# MB1297_MCU1.net
KiCad netlist of a schematic drawn in Altium Designer
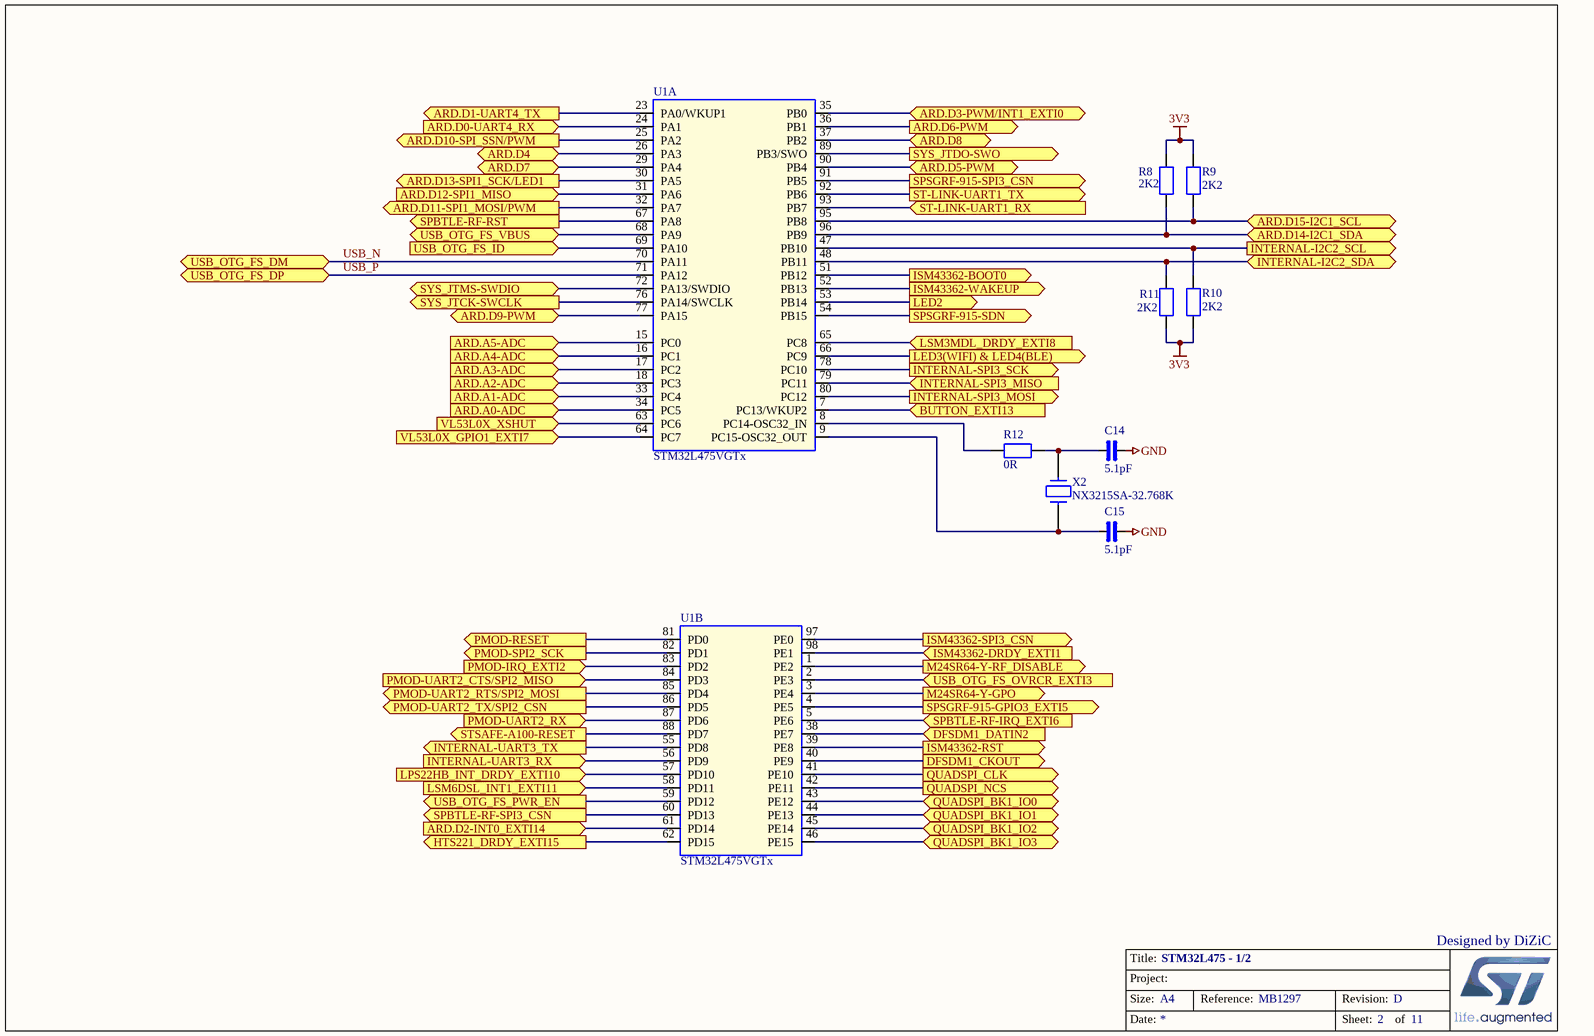
[diagram p0: MB1297_MCU1.SchDoc]

(export (version "E")
  (design (tool "Eeschema 10.0.6"))
  (components
    (comp (ref "C14")
      (value "5.1pF")
      (footprint "0402_CAP_NPOL")
      (description "Capacitor_not polarized")
      (libsource (lib "ST_Lib3D") (part "CAP_NPOL"))
    )
    (comp (ref "C15")
      (value "5.1pF")
      (footprint "0402_CAP_NPOL")
      (description "Capacitor_not polarized")
      (libsource (lib "ST_Lib3D") (part "CAP_NPOL"))
    )
    (comp (ref "R8")
      (value "2K2")
      (footprint "0402_RES")
      (description "Resistor")
      (libsource (lib "ST_Lib3D") (part "RES"))
    )
    (comp (ref "R9")
      (value "2K2")
      (footprint "0402_RES")
      (description "Resistor")
      (libsource (lib "ST_Lib3D") (part "RES"))
    )
    (comp (ref "R10")
      (value "2K2")
      (footprint "0402_RES")
      (description "Resistor")
      (libsource (lib "ST_Lib3D") (part "RES"))
    )
    (comp (ref "R11")
      (value "2K2")
      (footprint "0402_RES")
      (description "Resistor")
      (libsource (lib "ST_Lib3D") (part "RES"))
    )
    (comp (ref "R12")
      (value "0R")
      (footprint "0402_RES")
      (description "Resistor")
      (libsource (lib "ST_Lib3D") (part "RES"))
    )
    (comp (ref "U1")
      (value "STM32L475VGTx")
      (footprint "ST_Lib3D:LQFP100 14x14x1.6")
      (libsource (lib "ST_Lib3D") (part "STM32L475VGTx"))
    )
    (comp (ref "X2")
      (value "NX3215SA-32.768K")
      (footprint "CRY_NX3215SA_2P")
      (description "Crystal 32.768kHz, 6pF, -+20PPM, R=50K, SMD")
      (libsource (lib "MCD_TEMP_PCH") (part "XTAL_32K_NX3215SA"))
    )
  )
  (nets
    (net (code "1") (name "/ARD.A0-ADC") (class "Default")
      (node (ref "U1") (pin "34") (pinfunction "PC5_34") (pintype "passive"))
    )
    (net (code "2") (name "/ARD.A1-ADC") (class "Default")
      (node (ref "U1") (pin "33") (pinfunction "PC4_33") (pintype "passive"))
    )
    (net (code "3") (name "/ARD.A2-ADC") (class "Default")
      (node (ref "U1") (pin "18") (pinfunction "PC3_18") (pintype "passive"))
    )
    (net (code "4") (name "/ARD.A3-ADC") (class "Default")
      (node (ref "U1") (pin "17") (pinfunction "PC2_17") (pintype "passive"))
    )
    (net (code "5") (name "/ARD.A4-ADC") (class "Default")
      (node (ref "U1") (pin "16") (pinfunction "PC1_16") (pintype "passive"))
    )
    (net (code "6") (name "/ARD.A5-ADC") (class "Default")
      (node (ref "U1") (pin "15") (pinfunction "PC0_15") (pintype "passive"))
    )
    (net (code "7") (name "/ARD.D0-UART4_RX") (class "Default")
      (node (ref "U1") (pin "24") (pinfunction "PA1_24") (pintype "passive"))
    )
    (net (code "8") (name "/ARD.D1-UART4_TX") (class "Default")
      (node (ref "U1") (pin "23") (pinfunction "PA0/WKUP1_23") (pintype "passive"))
    )
    (net (code "9") (name "/ARD.D2-INT0_EXTI14") (class "Default")
      (node (ref "U1") (pin "61") (pinfunction "PD14_61") (pintype "passive"))
    )
    (net (code "10") (name "/ARD.D3-PWM{slash}INT1_EXTI0") (class "Default")
      (node (ref "U1") (pin "35") (pinfunction "PB0_35") (pintype "passive"))
    )
    (net (code "11") (name "/ARD.D4") (class "Default")
      (node (ref "U1") (pin "26") (pinfunction "PA3_26") (pintype "passive"))
    )
    (net (code "12") (name "/ARD.D5-PWM") (class "Default")
      (node (ref "U1") (pin "90") (pinfunction "PB4_90") (pintype "passive"))
    )
    (net (code "13") (name "/ARD.D6-PWM") (class "Default")
      (node (ref "U1") (pin "36") (pinfunction "PB1_36") (pintype "passive"))
    )
    (net (code "14") (name "/ARD.D7") (class "Default")
      (node (ref "U1") (pin "29") (pinfunction "PA4_29") (pintype "passive"))
    )
    (net (code "15") (name "/ARD.D8") (class "Default")
      (node (ref "U1") (pin "37") (pinfunction "PB2_37") (pintype "passive"))
    )
    (net (code "16") (name "/ARD.D9-PWM") (class "Default")
      (node (ref "U1") (pin "77") (pinfunction "PA15_77") (pintype "passive"))
    )
    (net (code "17") (name "/ARD.D10-SPI_SSN{slash}PWM") (class "Default")
      (node (ref "U1") (pin "25") (pinfunction "PA2_25") (pintype "passive"))
    )
    (net (code "18") (name "/ARD.D11-SPI1_MOSI{slash}PWM") (class "Default")
      (node (ref "U1") (pin "32") (pinfunction "PA7_32") (pintype "passive"))
    )
    (net (code "19") (name "/ARD.D12-SPI1_MISO") (class "Default")
      (node (ref "U1") (pin "31") (pinfunction "PA6_31") (pintype "passive"))
    )
    (net (code "20") (name "/ARD.D13-SPI1_SCK{slash}LED1") (class "Default")
      (node (ref "U1") (pin "30") (pinfunction "PA5_30") (pintype "passive"))
    )
    (net (code "21") (name "/ARD.D14-I2C1_SDA") (class "Default")
      (node (ref "R8") (pin "2") (pinfunction "2_2") (pintype "passive"))
      (node (ref "U1") (pin "96") (pinfunction "PB9_96") (pintype "passive"))
    )
    (net (code "22") (name "/ARD.D15-I2C1_SCL") (class "Default")
      (node (ref "R9") (pin "2") (pinfunction "2_2") (pintype "passive"))
      (node (ref "U1") (pin "95") (pinfunction "PB8_95") (pintype "passive"))
    )
    (net (code "23") (name "/BUTTON_EXTI13") (class "Default")
      (node (ref "U1") (pin "7") (pinfunction "PC13/WKUP2_7") (pintype "passive"))
    )
    (net (code "24") (name "/DFSDM1_CKOUT") (class "Default")
      (node (ref "U1") (pin "40") (pinfunction "PE9_40") (pintype "passive"))
    )
    (net (code "25") (name "/DFSDM1_DATIN2") (class "Default")
      (node (ref "U1") (pin "38") (pinfunction "PE7_38") (pintype "passive"))
    )
    (net (code "26") (name "/HTS221_DRDY_EXTI15") (class "Default")
      (node (ref "U1") (pin "62") (pinfunction "PD15_62") (pintype "passive"))
    )
    (net (code "27") (name "/INTERNAL-I2C2_SCL") (class "Default")
      (node (ref "R10") (pin "2") (pinfunction "2_2") (pintype "passive"))
      (node (ref "U1") (pin "47") (pinfunction "PB10_47") (pintype "passive"))
    )
    (net (code "28") (name "/INTERNAL-I2C2_SDA") (class "Default")
      (node (ref "R11") (pin "2") (pinfunction "2_2") (pintype "passive"))
      (node (ref "U1") (pin "48") (pinfunction "PB11_48") (pintype "passive"))
    )
    (net (code "29") (name "/INTERNAL-SPI3_MISO") (class "Default")
      (node (ref "U1") (pin "79") (pinfunction "PC11_79") (pintype "passive"))
    )
    (net (code "30") (name "/INTERNAL-SPI3_MOSI") (class "Default")
      (node (ref "U1") (pin "80") (pinfunction "PC12_80") (pintype "passive"))
    )
    (net (code "31") (name "/INTERNAL-SPI3_SCK") (class "Default")
      (node (ref "U1") (pin "78") (pinfunction "PC10_78") (pintype "passive"))
    )
    (net (code "32") (name "/INTERNAL-UART3_RX") (class "Default")
      (node (ref "U1") (pin "56") (pinfunction "PD9_56") (pintype "passive"))
    )
    (net (code "33") (name "/INTERNAL-UART3_TX") (class "Default")
      (node (ref "U1") (pin "55") (pinfunction "PD8_55") (pintype "passive"))
    )
    (net (code "34") (name "/ISM43362-BOOT0") (class "Default")
      (node (ref "U1") (pin "51") (pinfunction "PB12_51") (pintype "passive"))
    )
    (net (code "35") (name "/ISM43362-DRDY_EXTI1") (class "Default")
      (node (ref "U1") (pin "98") (pinfunction "PE1_98") (pintype "passive"))
    )
    (net (code "36") (name "/ISM43362-RST") (class "Default")
      (node (ref "U1") (pin "39") (pinfunction "PE8_39") (pintype "passive"))
    )
    (net (code "37") (name "/ISM43362-SPI3_CSN") (class "Default")
      (node (ref "U1") (pin "97") (pinfunction "PE0_97") (pintype "passive"))
    )
    (net (code "38") (name "/ISM43362-WAKEUP") (class "Default")
      (node (ref "U1") (pin "52") (pinfunction "PB13_52") (pintype "passive"))
    )
    (net (code "39") (name "/LED2") (class "Default")
      (node (ref "U1") (pin "53") (pinfunction "PB14_53") (pintype "passive"))
    )
    (net (code "40") (name "/LED3(WIFI) & LED4(BLE)") (class "Default")
      (node (ref "U1") (pin "66") (pinfunction "PC9_66") (pintype "passive"))
    )
    (net (code "41") (name "/LPS22HB_INT_DRDY_EXTI10") (class "Default")
      (node (ref "U1") (pin "57") (pinfunction "PD10_57") (pintype "passive"))
    )
    (net (code "42") (name "/LSM3MDL_DRDY_EXTI8") (class "Default")
      (node (ref "U1") (pin "65") (pinfunction "PC8_65") (pintype "passive"))
    )
    (net (code "43") (name "/LSM6DSL_INT1_EXTI11") (class "Default")
      (node (ref "U1") (pin "58") (pinfunction "PD11_58") (pintype "passive"))
    )
    (net (code "44") (name "/M24SR64-Y-GPO") (class "Default")
      (node (ref "U1") (pin "3") (pinfunction "PE4_3") (pintype "passive"))
    )
    (net (code "45") (name "/M24SR64-Y-RF_DISABLE") (class "Default")
      (node (ref "U1") (pin "1") (pinfunction "PE2_1") (pintype "passive"))
    )
    (net (code "46") (name "/PMOD-IRQ_EXTI2") (class "Default")
      (node (ref "U1") (pin "83") (pinfunction "PD2_83") (pintype "passive"))
    )
    (net (code "47") (name "/PMOD-RESET") (class "Default")
      (node (ref "U1") (pin "81") (pinfunction "PD0_81") (pintype "passive"))
    )
    (net (code "48") (name "/PMOD-SPI2_SCK") (class "Default")
      (node (ref "U1") (pin "82") (pinfunction "PD1_82") (pintype "passive"))
    )
    (net (code "49") (name "/PMOD-UART2_CTS{slash}SPI2_MISO") (class "Default")
      (node (ref "U1") (pin "84") (pinfunction "PD3_84") (pintype "passive"))
    )
    (net (code "50") (name "/PMOD-UART2_RTS{slash}SPI2_MOSI") (class "Default")
      (node (ref "U1") (pin "85") (pinfunction "PD4_85") (pintype "passive"))
    )
    (net (code "51") (name "/PMOD-UART2_RX") (class "Default")
      (node (ref "U1") (pin "87") (pinfunction "PD6_87") (pintype "passive"))
    )
    (net (code "52") (name "/PMOD-UART2_TX{slash}SPI2_CSN") (class "Default")
      (node (ref "U1") (pin "86") (pinfunction "PD5_86") (pintype "passive"))
    )
    (net (code "53") (name "/QUADSPI_BK1_IO0") (class "Default")
      (node (ref "U1") (pin "43") (pinfunction "PE12_43") (pintype "passive"))
    )
    (net (code "54") (name "/QUADSPI_BK1_IO1") (class "Default")
      (node (ref "U1") (pin "44") (pinfunction "PE13_44") (pintype "passive"))
    )
    (net (code "55") (name "/QUADSPI_BK1_IO2") (class "Default")
      (node (ref "U1") (pin "45") (pinfunction "PE14_45") (pintype "passive"))
    )
    (net (code "56") (name "/QUADSPI_BK1_IO3") (class "Default")
      (node (ref "U1") (pin "46") (pinfunction "PE15_46") (pintype "passive"))
    )
    (net (code "57") (name "/QUADSPI_CLK") (class "Default")
      (node (ref "U1") (pin "41") (pinfunction "PE10_41") (pintype "passive"))
    )
    (net (code "58") (name "/QUADSPI_NCS") (class "Default")
      (node (ref "U1") (pin "42") (pinfunction "PE11_42") (pintype "passive"))
    )
    (net (code "59") (name "/SPBTLE-RF-IRQ_EXTI6") (class "Default")
      (node (ref "U1") (pin "5") (pinfunction "PE6_5") (pintype "passive"))
    )
    (net (code "60") (name "/SPBTLE-RF-RST") (class "Default")
      (node (ref "U1") (pin "67") (pinfunction "PA8_67") (pintype "passive"))
    )
    (net (code "61") (name "/SPBTLE-RF-SPI3_CSN") (class "Default")
      (node (ref "U1") (pin "60") (pinfunction "PD13_60") (pintype "passive"))
    )
    (net (code "62") (name "/SPSGRF-915-GPIO3_EXTI5") (class "Default")
      (node (ref "U1") (pin "4") (pinfunction "PE5_4") (pintype "passive"))
    )
    (net (code "63") (name "/SPSGRF-915-SDN") (class "Default")
      (node (ref "U1") (pin "54") (pinfunction "PB15_54") (pintype "passive"))
    )
    (net (code "64") (name "/SPSGRF-915-SPI3_CSN") (class "Default")
      (node (ref "U1") (pin "91") (pinfunction "PB5_91") (pintype "passive"))
    )
    (net (code "65") (name "/ST-LINK-UART1_RX") (class "Default")
      (node (ref "U1") (pin "93") (pinfunction "PB7_93") (pintype "passive"))
    )
    (net (code "66") (name "/ST-LINK-UART1_TX") (class "Default")
      (node (ref "U1") (pin "92") (pinfunction "PB6_92") (pintype "passive"))
    )
    (net (code "67") (name "/STSAFE-A100-RESET") (class "Default")
      (node (ref "U1") (pin "88") (pinfunction "PD7_88") (pintype "passive"))
    )
    (net (code "68") (name "/SYS_JTCK-SWCLK") (class "Default")
      (node (ref "U1") (pin "76") (pinfunction "PA14/SWCLK_76") (pintype "passive"))
    )
    (net (code "69") (name "/SYS_JTDO-SWO") (class "Default")
      (node (ref "U1") (pin "89") (pinfunction "PB3/SWO_89") (pintype "passive"))
    )
    (net (code "70") (name "/SYS_JTMS-SWDIO") (class "Default")
      (node (ref "U1") (pin "72") (pinfunction "PA13/SWDIO_72") (pintype "passive"))
    )
    (net (code "71") (name "/USB_N") (class "Default")
      (node (ref "U1") (pin "70") (pinfunction "PA11_70") (pintype "passive"))
    )
    (net (code "72") (name "/USB_OTG_FS_ID") (class "Default")
      (node (ref "U1") (pin "69") (pinfunction "PA10_69") (pintype "passive"))
    )
    (net (code "73") (name "/USB_OTG_FS_OVRCR_EXTI3") (class "Default")
      (node (ref "U1") (pin "2") (pinfunction "PE3_2") (pintype "passive"))
    )
    (net (code "74") (name "/USB_OTG_FS_PWR_EN") (class "Default")
      (node (ref "U1") (pin "59") (pinfunction "PD12_59") (pintype "passive"))
    )
    (net (code "75") (name "/USB_OTG_FS_VBUS") (class "Default")
      (node (ref "U1") (pin "68") (pinfunction "PA9_68") (pintype "passive"))
    )
    (net (code "76") (name "/USB_P") (class "Default")
      (node (ref "U1") (pin "71") (pinfunction "PA12_71") (pintype "passive"))
    )
    (net (code "77") (name "/VL53L0X_GPIO1_EXTI7") (class "Default")
      (node (ref "U1") (pin "64") (pinfunction "PC7_64") (pintype "passive"))
    )
    (net (code "78") (name "/VL53L0X_XSHUT") (class "Default")
      (node (ref "U1") (pin "63") (pinfunction "PC6_63") (pintype "passive"))
    )
    (net (code "79") (name "3V3") (class "Default")
      (node (ref "R10") (pin "1") (pinfunction "1_1") (pintype "passive"))
      (node (ref "R11") (pin "1") (pinfunction "1_1") (pintype "passive"))
      (node (ref "R8") (pin "1") (pinfunction "1_1") (pintype "passive"))
      (node (ref "R9") (pin "1") (pinfunction "1_1") (pintype "passive"))
    )
    (net (code "80") (name "GND") (class "Default")
      (node (ref "C14") (pin "2") (pinfunction "2_2") (pintype "passive"))
      (node (ref "C15") (pin "2") (pinfunction "2_2") (pintype "passive"))
    )
    (net (code "81") (name "Net-(C14-Pad1)") (class "Default")
      (node (ref "C14") (pin "1") (pinfunction "1_1") (pintype "passive"))
      (node (ref "R12") (pin "2") (pinfunction "2_2") (pintype "passive"))
      (node (ref "X2") (pin "1") (pinfunction "1_1") (pintype "passive"))
    )
    (net (code "82") (name "Net-(U1A-PC14-OSC32_IN)") (class "Default")
      (node (ref "R12") (pin "1") (pinfunction "1_1") (pintype "passive"))
      (node (ref "U1") (pin "8") (pinfunction "PC14-OSC32_IN_8") (pintype "passive"))
    )
    (net (code "83") (name "Net-(U1A-PC15-OSC32_OUT)") (class "Default")
      (node (ref "C15") (pin "1") (pinfunction "1_1") (pintype "passive"))
      (node (ref "U1") (pin "9") (pinfunction "PC15-OSC32_OUT_9") (pintype "passive"))
      (node (ref "X2") (pin "2") (pinfunction "2_2") (pintype "passive"))
    )
  )
)
